# DDR3_Termination.net
KiCad netlist of a schematic drawn in Altium Designer
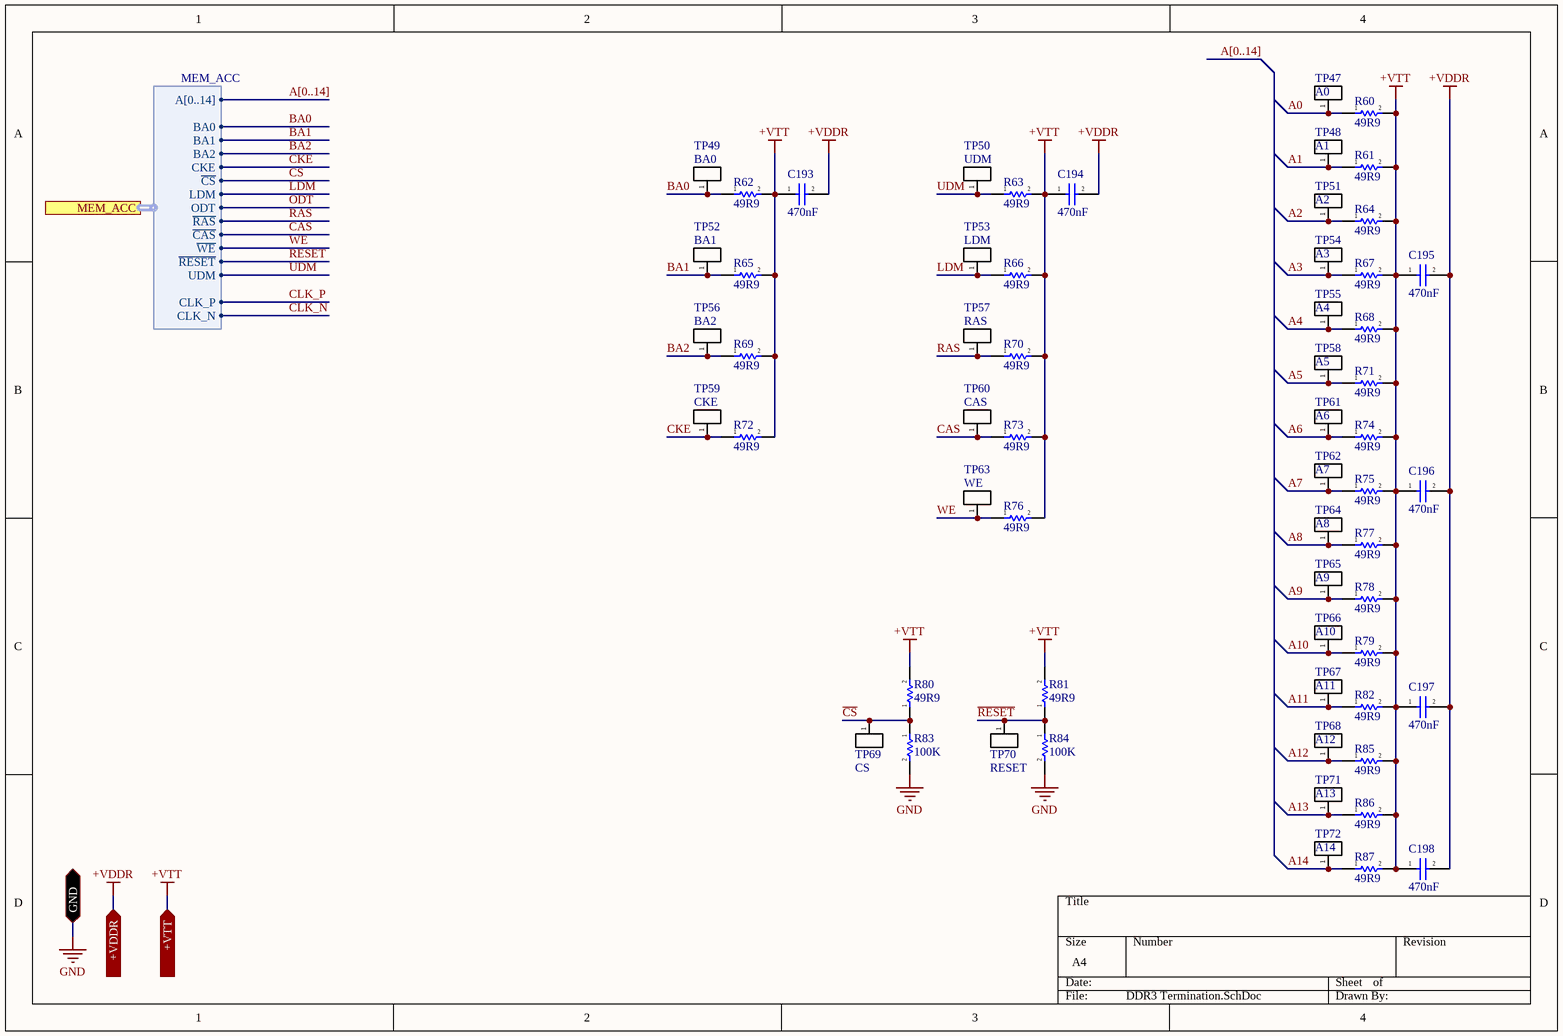
[diagram p0: DDR3 Termination.SchDoc]

(export (version "E")
  (design (tool "Eeschema 10.0.6"))
  (components
    (comp (ref "C193")
      (value "470nF")
      (footprint "CAP_0402")
      (description "Generic SMT Ceramic Capacitor")
      (libsource (lib "Symbols") (part "CAP_CER"))
    )
    (comp (ref "C194")
      (value "470nF")
      (footprint "CAP_0402")
      (description "Generic SMT Ceramic Capacitor")
      (libsource (lib "Symbols") (part "CAP_CER"))
    )
    (comp (ref "C195")
      (value "470nF")
      (footprint "CAP_0402")
      (description "Generic SMT Ceramic Capacitor")
      (libsource (lib "Symbols") (part "CAP_CER"))
    )
    (comp (ref "C196")
      (value "470nF")
      (footprint "CAP_0402")
      (description "Generic SMT Ceramic Capacitor")
      (libsource (lib "Symbols") (part "CAP_CER"))
    )
    (comp (ref "C197")
      (value "470nF")
      (footprint "CAP_0402")
      (description "Generic SMT Ceramic Capacitor")
      (libsource (lib "Symbols") (part "CAP_CER"))
    )
    (comp (ref "C198")
      (value "470nF")
      (footprint "CAP_0402")
      (description "Generic SMT Ceramic Capacitor")
      (libsource (lib "Symbols") (part "CAP_CER"))
    )
    (comp (ref "R60")
      (value "49R9")
      (footprint "RES_0402")
      (description "Resistor")
      (fields (field (name "POWER") "1/8W") (field (name "TOLERANCE") "0.5%"))
      (libsource (lib "Symbols") (part "RESISTOR"))
    )
    (comp (ref "R61")
      (value "49R9")
      (footprint "RES_0402")
      (description "Resistor")
      (fields (field (name "POWER") "1/8W") (field (name "TOLERANCE") "0.5%"))
      (libsource (lib "Symbols") (part "RESISTOR"))
    )
    (comp (ref "R62")
      (value "49R9")
      (footprint "RES_0402")
      (description "Resistor")
      (fields (field (name "POWER") "1/8W") (field (name "TOLERANCE") "0.5%"))
      (libsource (lib "Symbols") (part "RESISTOR"))
    )
    (comp (ref "R63")
      (value "49R9")
      (footprint "RES_0402")
      (description "Resistor")
      (fields (field (name "POWER") "1/8W") (field (name "TOLERANCE") "0.5%"))
      (libsource (lib "Symbols") (part "RESISTOR"))
    )
    (comp (ref "R64")
      (value "49R9")
      (footprint "RES_0402")
      (description "Resistor")
      (fields (field (name "POWER") "1/8W") (field (name "TOLERANCE") "0.5%"))
      (libsource (lib "Symbols") (part "RESISTOR"))
    )
    (comp (ref "R65")
      (value "49R9")
      (footprint "RES_0402")
      (description "Resistor")
      (fields (field (name "POWER") "1/8W") (field (name "TOLERANCE") "0.5%"))
      (libsource (lib "Symbols") (part "RESISTOR"))
    )
    (comp (ref "R66")
      (value "49R9")
      (footprint "RES_0402")
      (description "Resistor")
      (fields (field (name "POWER") "1/8W") (field (name "TOLERANCE") "0.5%"))
      (libsource (lib "Symbols") (part "RESISTOR"))
    )
    (comp (ref "R67")
      (value "49R9")
      (footprint "RES_0402")
      (description "Resistor")
      (fields (field (name "POWER") "1/8W") (field (name "TOLERANCE") "0.5%"))
      (libsource (lib "Symbols") (part "RESISTOR"))
    )
    (comp (ref "R68")
      (value "49R9")
      (footprint "RES_0402")
      (description "Resistor")
      (fields (field (name "POWER") "1/8W") (field (name "TOLERANCE") "0.5%"))
      (libsource (lib "Symbols") (part "RESISTOR"))
    )
    (comp (ref "R69")
      (value "49R9")
      (footprint "RES_0402")
      (description "Resistor")
      (fields (field (name "POWER") "1/8W") (field (name "TOLERANCE") "0.5%"))
      (libsource (lib "Symbols") (part "RESISTOR"))
    )
    (comp (ref "R70")
      (value "49R9")
      (footprint "RES_0402")
      (description "Resistor")
      (fields (field (name "POWER") "1/8W") (field (name "TOLERANCE") "0.5%"))
      (libsource (lib "Symbols") (part "RESISTOR"))
    )
    (comp (ref "R71")
      (value "49R9")
      (footprint "RES_0402")
      (description "Resistor")
      (fields (field (name "POWER") "1/8W") (field (name "TOLERANCE") "0.5%"))
      (libsource (lib "Symbols") (part "RESISTOR"))
    )
    (comp (ref "R72")
      (value "49R9")
      (footprint "RES_0402")
      (description "Resistor")
      (fields (field (name "POWER") "1/8W") (field (name "TOLERANCE") "0.5%"))
      (libsource (lib "Symbols") (part "RESISTOR"))
    )
    (comp (ref "R73")
      (value "49R9")
      (footprint "RES_0402")
      (description "Resistor")
      (fields (field (name "POWER") "1/8W") (field (name "TOLERANCE") "0.5%"))
      (libsource (lib "Symbols") (part "RESISTOR"))
    )
    (comp (ref "R74")
      (value "49R9")
      (footprint "RES_0402")
      (description "Resistor")
      (fields (field (name "POWER") "1/8W") (field (name "TOLERANCE") "0.5%"))
      (libsource (lib "Symbols") (part "RESISTOR"))
    )
    (comp (ref "R75")
      (value "49R9")
      (footprint "RES_0402")
      (description "Resistor")
      (fields (field (name "POWER") "1/8W") (field (name "TOLERANCE") "0.5%"))
      (libsource (lib "Symbols") (part "RESISTOR"))
    )
    (comp (ref "R76")
      (value "49R9")
      (footprint "RES_0402")
      (description "Resistor")
      (fields (field (name "POWER") "1/8W") (field (name "TOLERANCE") "0.5%"))
      (libsource (lib "Symbols") (part "RESISTOR"))
    )
    (comp (ref "R77")
      (value "49R9")
      (footprint "RES_0402")
      (description "Resistor")
      (fields (field (name "POWER") "1/8W") (field (name "TOLERANCE") "0.5%"))
      (libsource (lib "Symbols") (part "RESISTOR"))
    )
    (comp (ref "R78")
      (value "49R9")
      (footprint "RES_0402")
      (description "Resistor")
      (fields (field (name "POWER") "1/8W") (field (name "TOLERANCE") "0.5%"))
      (libsource (lib "Symbols") (part "RESISTOR"))
    )
    (comp (ref "R79")
      (value "49R9")
      (footprint "RES_0402")
      (description "Resistor")
      (fields (field (name "POWER") "1/8W") (field (name "TOLERANCE") "0.5%"))
      (libsource (lib "Symbols") (part "RESISTOR"))
    )
    (comp (ref "R80")
      (value "49R9")
      (footprint "RES_0402")
      (description "Resistor")
      (fields (field (name "POWER") "1/8W") (field (name "TOLERANCE") "0.5%"))
      (libsource (lib "Symbols") (part "RESISTOR"))
    )
    (comp (ref "R81")
      (value "49R9")
      (footprint "RES_0402")
      (description "Resistor")
      (fields (field (name "POWER") "1/8W") (field (name "TOLERANCE") "0.5%"))
      (libsource (lib "Symbols") (part "RESISTOR"))
    )
    (comp (ref "R82")
      (value "49R9")
      (footprint "RES_0402")
      (description "Resistor")
      (fields (field (name "POWER") "1/8W") (field (name "TOLERANCE") "0.5%"))
      (libsource (lib "Symbols") (part "RESISTOR"))
    )
    (comp (ref "R83")
      (value "100K")
      (footprint "RES_0603")
      (description "Resistor")
      (fields (field (name "POWER") "1/16W") (field (name "TOLERANCE") "10%"))
      (libsource (lib "Symbols") (part "RESISTOR"))
    )
    (comp (ref "R84")
      (value "100K")
      (footprint "RES_0603")
      (description "Resistor")
      (fields (field (name "POWER") "1/16W") (field (name "TOLERANCE") "10%"))
      (libsource (lib "Symbols") (part "RESISTOR"))
    )
    (comp (ref "R85")
      (value "49R9")
      (footprint "RES_0402")
      (description "Resistor")
      (fields (field (name "POWER") "1/8W") (field (name "TOLERANCE") "0.5%"))
      (libsource (lib "Symbols") (part "RESISTOR"))
    )
    (comp (ref "R86")
      (value "49R9")
      (footprint "RES_0402")
      (description "Resistor")
      (fields (field (name "POWER") "1/8W") (field (name "TOLERANCE") "0.5%"))
      (libsource (lib "Symbols") (part "RESISTOR"))
    )
    (comp (ref "R87")
      (value "49R9")
      (footprint "RES_0402")
      (description "Resistor")
      (fields (field (name "POWER") "1/8W") (field (name "TOLERANCE") "0.5%"))
      (libsource (lib "Symbols") (part "RESISTOR"))
    )
    (comp (ref "TP47")
      (value "A0")
      (footprint "TP_PAD_TINY")
      (description "Test Point")
      (libsource (lib "Symbols") (part "TESTPOINT"))
    )
    (comp (ref "TP48")
      (value "A1")
      (footprint "TP_PAD_TINY")
      (description "Test Point")
      (libsource (lib "Symbols") (part "TESTPOINT"))
    )
    (comp (ref "TP49")
      (value "BA0")
      (footprint "TP_PAD_TINY")
      (description "Test Point")
      (libsource (lib "Symbols") (part "TESTPOINT"))
    )
    (comp (ref "TP50")
      (value "UDM")
      (footprint "TP_PAD_TINY")
      (description "Test Point")
      (libsource (lib "Symbols") (part "TESTPOINT"))
    )
    (comp (ref "TP51")
      (value "A2")
      (footprint "TP_PAD_TINY")
      (description "Test Point")
      (libsource (lib "Symbols") (part "TESTPOINT"))
    )
    (comp (ref "TP52")
      (value "BA1")
      (footprint "TP_PAD_TINY")
      (description "Test Point")
      (libsource (lib "Symbols") (part "TESTPOINT"))
    )
    (comp (ref "TP53")
      (value "LDM")
      (footprint "TP_PAD_TINY")
      (description "Test Point")
      (libsource (lib "Symbols") (part "TESTPOINT"))
    )
    (comp (ref "TP54")
      (value "A3")
      (footprint "TP_PAD_TINY")
      (description "Test Point")
      (libsource (lib "Symbols") (part "TESTPOINT"))
    )
    (comp (ref "TP55")
      (value "A4")
      (footprint "TP_PAD_TINY")
      (description "Test Point")
      (libsource (lib "Symbols") (part "TESTPOINT"))
    )
    (comp (ref "TP56")
      (value "BA2")
      (footprint "TP_PAD_TINY")
      (description "Test Point")
      (libsource (lib "Symbols") (part "TESTPOINT"))
    )
    (comp (ref "TP57")
      (value "RAS")
      (footprint "TP_PAD_TINY")
      (description "Test Point")
      (libsource (lib "Symbols") (part "TESTPOINT"))
    )
    (comp (ref "TP58")
      (value "A5")
      (footprint "TP_PAD_TINY")
      (description "Test Point")
      (libsource (lib "Symbols") (part "TESTPOINT"))
    )
    (comp (ref "TP59")
      (value "CKE")
      (footprint "TP_PAD_TINY")
      (description "Test Point")
      (libsource (lib "Symbols") (part "TESTPOINT"))
    )
    (comp (ref "TP60")
      (value "CAS")
      (footprint "TP_PAD_TINY")
      (description "Test Point")
      (libsource (lib "Symbols") (part "TESTPOINT"))
    )
    (comp (ref "TP61")
      (value "A6")
      (footprint "TP_PAD_TINY")
      (description "Test Point")
      (libsource (lib "Symbols") (part "TESTPOINT"))
    )
    (comp (ref "TP62")
      (value "A7")
      (footprint "TP_PAD_TINY")
      (description "Test Point")
      (libsource (lib "Symbols") (part "TESTPOINT"))
    )
    (comp (ref "TP63")
      (value "WE")
      (footprint "TP_PAD_TINY")
      (description "Test Point")
      (libsource (lib "Symbols") (part "TESTPOINT"))
    )
    (comp (ref "TP64")
      (value "A8")
      (footprint "TP_PAD_TINY")
      (description "Test Point")
      (libsource (lib "Symbols") (part "TESTPOINT"))
    )
    (comp (ref "TP65")
      (value "A9")
      (footprint "TP_PAD_TINY")
      (description "Test Point")
      (libsource (lib "Symbols") (part "TESTPOINT"))
    )
    (comp (ref "TP66")
      (value "A10")
      (footprint "TP_PAD_TINY")
      (description "Test Point")
      (libsource (lib "Symbols") (part "TESTPOINT"))
    )
    (comp (ref "TP67")
      (value "A11")
      (footprint "TP_PAD_TINY")
      (description "Test Point")
      (libsource (lib "Symbols") (part "TESTPOINT"))
    )
    (comp (ref "TP68")
      (value "A12")
      (footprint "TP_PAD_TINY")
      (description "Test Point")
      (libsource (lib "Symbols") (part "TESTPOINT"))
    )
    (comp (ref "TP69")
      (value "CS")
      (footprint "TP_PAD_TINY")
      (description "Test Point")
      (libsource (lib "Symbols") (part "TESTPOINT"))
    )
    (comp (ref "TP70")
      (value "RESET")
      (footprint "TP_PAD_TINY")
      (description "Test Point")
      (libsource (lib "Symbols") (part "TESTPOINT"))
    )
    (comp (ref "TP71")
      (value "A13")
      (footprint "TP_PAD_TINY")
      (description "Test Point")
      (libsource (lib "Symbols") (part "TESTPOINT"))
    )
    (comp (ref "TP72")
      (value "A14")
      (footprint "TP_PAD_TINY")
      (description "Test Point")
      (libsource (lib "Symbols") (part "TESTPOINT"))
    )
  )
  (nets
    (net (code "2") (name "+VDDR") (class "Default")
      (node (ref "C193") (pin "2") (pinfunction "2_2") (pintype "passive"))
      (node (ref "C194") (pin "2") (pinfunction "2_2") (pintype "passive"))
      (node (ref "C195") (pin "2") (pinfunction "2_2") (pintype "passive"))
      (node (ref "C196") (pin "2") (pinfunction "2_2") (pintype "passive"))
      (node (ref "C197") (pin "2") (pinfunction "2_2") (pintype "passive"))
      (node (ref "C198") (pin "2") (pinfunction "2_2") (pintype "passive"))
    )
    (net (code "3") (name "+VTT") (class "Default")
      (node (ref "C193") (pin "1") (pinfunction "1_1") (pintype "passive"))
      (node (ref "C194") (pin "1") (pinfunction "1_1") (pintype "passive"))
      (node (ref "C195") (pin "1") (pinfunction "1_1") (pintype "passive"))
      (node (ref "C196") (pin "1") (pinfunction "1_1") (pintype "passive"))
      (node (ref "C197") (pin "1") (pinfunction "1_1") (pintype "passive"))
      (node (ref "C198") (pin "1") (pinfunction "1_1") (pintype "passive"))
      (node (ref "R60") (pin "2") (pinfunction "2_2") (pintype "passive"))
      (node (ref "R61") (pin "2") (pinfunction "2_2") (pintype "passive"))
      (node (ref "R62") (pin "2") (pinfunction "2_2") (pintype "passive"))
      (node (ref "R63") (pin "2") (pinfunction "2_2") (pintype "passive"))
      (node (ref "R64") (pin "2") (pinfunction "2_2") (pintype "passive"))
      (node (ref "R65") (pin "2") (pinfunction "2_2") (pintype "passive"))
      (node (ref "R66") (pin "2") (pinfunction "2_2") (pintype "passive"))
      (node (ref "R67") (pin "2") (pinfunction "2_2") (pintype "passive"))
      (node (ref "R68") (pin "2") (pinfunction "2_2") (pintype "passive"))
      (node (ref "R69") (pin "2") (pinfunction "2_2") (pintype "passive"))
      (node (ref "R70") (pin "2") (pinfunction "2_2") (pintype "passive"))
      (node (ref "R71") (pin "2") (pinfunction "2_2") (pintype "passive"))
      (node (ref "R72") (pin "2") (pinfunction "2_2") (pintype "passive"))
      (node (ref "R73") (pin "2") (pinfunction "2_2") (pintype "passive"))
      (node (ref "R74") (pin "2") (pinfunction "2_2") (pintype "passive"))
      (node (ref "R75") (pin "2") (pinfunction "2_2") (pintype "passive"))
      (node (ref "R76") (pin "2") (pinfunction "2_2") (pintype "passive"))
      (node (ref "R77") (pin "2") (pinfunction "2_2") (pintype "passive"))
      (node (ref "R78") (pin "2") (pinfunction "2_2") (pintype "passive"))
      (node (ref "R79") (pin "2") (pinfunction "2_2") (pintype "passive"))
      (node (ref "R80") (pin "2") (pinfunction "2_2") (pintype "passive"))
      (node (ref "R81") (pin "2") (pinfunction "2_2") (pintype "passive"))
      (node (ref "R82") (pin "2") (pinfunction "2_2") (pintype "passive"))
      (node (ref "R85") (pin "2") (pinfunction "2_2") (pintype "passive"))
      (node (ref "R86") (pin "2") (pinfunction "2_2") (pintype "passive"))
      (node (ref "R87") (pin "2") (pinfunction "2_2") (pintype "passive"))
    )
    (net (code "4") (name "/A0") (class "Default")
      (node (ref "R60") (pin "1") (pinfunction "1_1") (pintype "passive"))
      (node (ref "TP47") (pin "1") (pinfunction "A_1") (pintype "passive"))
    )
    (net (code "5") (name "/A1") (class "Default")
      (node (ref "R61") (pin "1") (pinfunction "1_1") (pintype "passive"))
      (node (ref "TP48") (pin "1") (pinfunction "A_1") (pintype "passive"))
    )
    (net (code "6") (name "/A2") (class "Default")
      (node (ref "R64") (pin "1") (pinfunction "1_1") (pintype "passive"))
      (node (ref "TP51") (pin "1") (pinfunction "A_1") (pintype "passive"))
    )
    (net (code "7") (name "/A3") (class "Default")
      (node (ref "R67") (pin "1") (pinfunction "1_1") (pintype "passive"))
      (node (ref "TP54") (pin "1") (pinfunction "A_1") (pintype "passive"))
    )
    (net (code "8") (name "/A4") (class "Default")
      (node (ref "R68") (pin "1") (pinfunction "1_1") (pintype "passive"))
      (node (ref "TP55") (pin "1") (pinfunction "A_1") (pintype "passive"))
    )
    (net (code "9") (name "/A5") (class "Default")
      (node (ref "R71") (pin "1") (pinfunction "1_1") (pintype "passive"))
      (node (ref "TP58") (pin "1") (pinfunction "A_1") (pintype "passive"))
    )
    (net (code "10") (name "/A6") (class "Default")
      (node (ref "R74") (pin "1") (pinfunction "1_1") (pintype "passive"))
      (node (ref "TP61") (pin "1") (pinfunction "A_1") (pintype "passive"))
    )
    (net (code "11") (name "/A7") (class "Default")
      (node (ref "R75") (pin "1") (pinfunction "1_1") (pintype "passive"))
      (node (ref "TP62") (pin "1") (pinfunction "A_1") (pintype "passive"))
    )
    (net (code "12") (name "/A8") (class "Default")
      (node (ref "R77") (pin "1") (pinfunction "1_1") (pintype "passive"))
      (node (ref "TP64") (pin "1") (pinfunction "A_1") (pintype "passive"))
    )
    (net (code "13") (name "/A9") (class "Default")
      (node (ref "R78") (pin "1") (pinfunction "1_1") (pintype "passive"))
      (node (ref "TP65") (pin "1") (pinfunction "A_1") (pintype "passive"))
    )
    (net (code "14") (name "/A10") (class "Default")
      (node (ref "R79") (pin "1") (pinfunction "1_1") (pintype "passive"))
      (node (ref "TP66") (pin "1") (pinfunction "A_1") (pintype "passive"))
    )
    (net (code "15") (name "/A11") (class "Default")
      (node (ref "R82") (pin "1") (pinfunction "1_1") (pintype "passive"))
      (node (ref "TP67") (pin "1") (pinfunction "A_1") (pintype "passive"))
    )
    (net (code "16") (name "/A12") (class "Default")
      (node (ref "R85") (pin "1") (pinfunction "1_1") (pintype "passive"))
      (node (ref "TP68") (pin "1") (pinfunction "A_1") (pintype "passive"))
    )
    (net (code "17") (name "/A13") (class "Default")
      (node (ref "R86") (pin "1") (pinfunction "1_1") (pintype "passive"))
      (node (ref "TP71") (pin "1") (pinfunction "A_1") (pintype "passive"))
    )
    (net (code "18") (name "/A14") (class "Default")
      (node (ref "R87") (pin "1") (pinfunction "1_1") (pintype "passive"))
      (node (ref "TP72") (pin "1") (pinfunction "A_1") (pintype "passive"))
    )
    (net (code "20") (name "/BA0") (class "Default")
      (node (ref "R62") (pin "1") (pinfunction "1_1") (pintype "passive"))
      (node (ref "TP49") (pin "1") (pinfunction "A_1") (pintype "passive"))
    )
    (net (code "21") (name "/BA1") (class "Default")
      (node (ref "R65") (pin "1") (pinfunction "1_1") (pintype "passive"))
      (node (ref "TP52") (pin "1") (pinfunction "A_1") (pintype "passive"))
    )
    (net (code "22") (name "/BA2") (class "Default")
      (node (ref "R69") (pin "1") (pinfunction "1_1") (pintype "passive"))
      (node (ref "TP56") (pin "1") (pinfunction "A_1") (pintype "passive"))
    )
    (net (code "23") (name "/CAS") (class "Default")
      (node (ref "R73") (pin "1") (pinfunction "1_1") (pintype "passive"))
      (node (ref "TP60") (pin "1") (pinfunction "A_1") (pintype "passive"))
    )
    (net (code "24") (name "/CKE") (class "Default")
      (node (ref "R72") (pin "1") (pinfunction "1_1") (pintype "passive"))
      (node (ref "TP59") (pin "1") (pinfunction "A_1") (pintype "passive"))
    )
    (net (code "27") (name "/LDM") (class "Default")
      (node (ref "R66") (pin "1") (pinfunction "1_1") (pintype "passive"))
      (node (ref "TP53") (pin "1") (pinfunction "A_1") (pintype "passive"))
    )
    (net (code "29") (name "/RAS") (class "Default")
      (node (ref "R70") (pin "1") (pinfunction "1_1") (pintype "passive"))
      (node (ref "TP57") (pin "1") (pinfunction "A_1") (pintype "passive"))
    )
    (net (code "30") (name "/UDM") (class "Default")
      (node (ref "R63") (pin "1") (pinfunction "1_1") (pintype "passive"))
      (node (ref "TP50") (pin "1") (pinfunction "A_1") (pintype "passive"))
    )
    (net (code "31") (name "/WE") (class "Default")
      (node (ref "R76") (pin "1") (pinfunction "1_1") (pintype "passive"))
      (node (ref "TP63") (pin "1") (pinfunction "A_1") (pintype "passive"))
    )
    (net (code "34") (name "/~{CS}") (class "Default")
      (node (ref "R80") (pin "1") (pinfunction "1_1") (pintype "passive"))
      (node (ref "R83") (pin "1") (pinfunction "1_1") (pintype "passive"))
      (node (ref "TP69") (pin "1") (pinfunction "A_1") (pintype "passive"))
    )
    (net (code "36") (name "/~{RESET}") (class "Default")
      (node (ref "R81") (pin "1") (pinfunction "1_1") (pintype "passive"))
      (node (ref "R84") (pin "1") (pinfunction "1_1") (pintype "passive"))
      (node (ref "TP70") (pin "1") (pinfunction "A_1") (pintype "passive"))
    )
    (net (code "38") (name "GND") (class "Default")
      (node (ref "R83") (pin "2") (pinfunction "2_2") (pintype "passive"))
      (node (ref "R84") (pin "2") (pinfunction "2_2") (pintype "passive"))
    )
  )
)
